# 06_Servo_Motor_ICs.net
KiCad netlist of a schematic drawn in Altium Designer
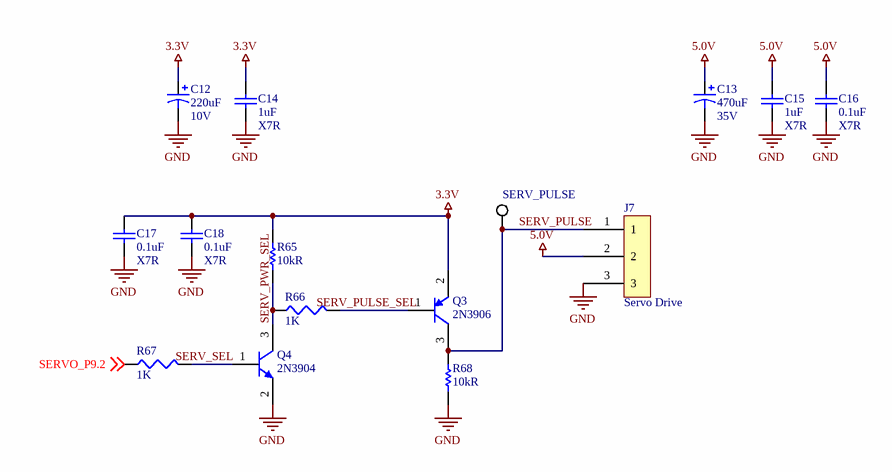
[diagram p0: 06_Servo_Motor_ICs.SchDoc]

(export (version "E")
  (design (tool "Eeschema 10.0.6"))
  (components
    (comp (ref "C12")
      (value "220uF")
      (footprint "CAPPR2-5x11")
      (description "Capacitor Al 105deg 220uF 10V 5X11")
      (fields
        (field (name "MANUFACTURER") "Rubycon")
        (field (name "MANUFACTURER PART NUMBER") "10YXJ220M5X11")
        (field (name "VOLTAGE") "10V")
      )
      (libsource (lib "ECE453") (part "Cap Pol1_1"))
    )
    (comp (ref "C13")
      (value "470uF")
      (footprint "CAPPR5-10x12.5")
      (description "CAP ALUM 470UF 20% 35V RADIAL")
      (fields
        (field (name "VOLTAGE") "35V")
        (field (name "MANUFACTURER") "Rubycon")
        (field (name "TOLERANCE") "20%")
      )
      (libsource (lib "ECE453") (part "Cap Pol3_1"))
    )
    (comp (ref "C14")
      (value "1uF")
      (footprint "CAP_0805")
      (description "CAP CER 1UF 50V X7R 0805")
      (fields
        (field (name "MANUFACTURER") "Samsung")
        (field (name "MANUFACTURER PART NUMBER") "CL21B105KBFNNNE")
        (field (name "DIELECTRIC") "X7R")
      )
      (libsource (lib "ECE453") (part "Cap_5"))
    )
    (comp (ref "C15")
      (value "1uF")
      (footprint "CAP_0805")
      (description "CAP CER 1UF 50V X7R 0805")
      (fields
        (field (name "MANUFACTURER") "Samsung")
        (field (name "MANUFACTURER PART NUMBER") "CL21B105KBFNNNE")
        (field (name "DIELECTRIC") "X7R")
      )
      (libsource (lib "ECE453") (part "Cap_5"))
    )
    (comp (ref "C16")
      (value "0.1uF")
      (footprint "CAP_0805")
      (description "Cap Ceramic 0.1uF 50V X7R 20% SMD 0805 125°C Plastic T/R")
      (fields
        (field (name "MANUFACTURER") "KEMET")
        (field (name "MANUFACTURER PART NUMBER") "C0805C104M5RAC7210")
        (field (name "DIELECTRIC") "X7R")
      )
      (libsource (lib "ECE453") (part "Cap_1"))
    )
    (comp (ref "C17")
      (value "0.1uF")
      (footprint "CAP_0805")
      (description "Cap Ceramic 0.1uF 50V X7R 20% SMD 0805 125°C Plastic T/R")
      (fields
        (field (name "MANUFACTURER") "KEMET")
        (field (name "MANUFACTURER PART NUMBER") "C0805C104M5RAC7210")
        (field (name "DIELECTRIC") "X7R")
      )
      (libsource (lib "ECE453") (part "Cap_1"))
    )
    (comp (ref "C18")
      (value "0.1uF")
      (footprint "CAP_0805")
      (description "Cap Ceramic 0.1uF 50V X7R 20% SMD 0805 125°C Plastic T/R")
      (fields
        (field (name "MANUFACTURER") "KEMET")
        (field (name "MANUFACTURER PART NUMBER") "C0805C104M5RAC7210")
        (field (name "DIELECTRIC") "X7R")
      )
      (libsource (lib "ECE453") (part "Cap_1"))
    )
    (comp (ref "J7")
      (value "Servo Drive")
      (footprint "3X1HDR")
      (description "Switch Slide N.O./N.C. SPDT Top Slide 0.2A 30VDC PC Pins Thru-Hole")
      (fields (field (name "MANUFACTURER") "E-Switch") (field (name "MANUFACTURER PART NUMBER") "EG1218"))
      (libsource (lib "ECE453") (part "3-Pin_1"))
    )
    (comp (ref "Q3")
      (value "2N3906")
      (footprint "SOT23-3M")
      (description "TRANS PNP 40V 0.2A SOT23")
      (fields
        (field (name "MANUFACTURER PART NUMBER") "MMBT3906LT1G")
        (field (name "MANUFACTURER") "ON Semiconductor")
      )
      (libsource (lib "ECE453") (part "2N3906"))
    )
    (comp (ref "Q4")
      (value "2N3904")
      (footprint "SOT23-3M")
      (description "NPN General Purpose Amplifier")
      (fields
        (field (name "MANUFACTURER PART NUMBER") "MMBT3904-7-F")
        (field (name "MANUFACTURER") "Diodes Incorporated")
      )
      (libsource (lib "ECE453") (part "2N3904"))
    )
    (comp (ref "R65")
      (value "RC0805FR-0710KL")
      (footprint "RESC2013X60X35NL10T20")
      (description "Chip Resistor, 10 KOhm, +/- 1%, 0.125 W, -55 to 155 degC, 0805 (2012 Metric), RoHS, Tape and Reel")
      (fields
        (field (name "MANUFACTURER") "Yageo")
        (field (name "TOLERANCE") "1%")
        (field (name "RESISTANCE") "10kR")
      )
      (libsource (lib "ECE453") (part "CMP-1659-00013-4"))
    )
    (comp (ref "R66")
      (value "1K")
      (footprint "ECE453:RES_0805")
      (description "Res Thick Film 0805 1K Ohm 1% 0.125W(1/8W) ±100ppm/C Pad SMD Automotive T/R")
      (fields
        (field (name "MANUFACTURER") "Stackpole Electronics")
        (field (name "MANUFACTURER PART NUMBER") "RMCF0805FT1K00")
      )
      (libsource (lib "ECE453") (part "Res3_1"))
    )
    (comp (ref "R67")
      (value "1K")
      (footprint "ECE453:RES_0805")
      (description "Res Thick Film 0805 1K Ohm 1% 0.125W(1/8W) ±100ppm/C Pad SMD Automotive T/R")
      (fields
        (field (name "MANUFACTURER") "Stackpole Electronics")
        (field (name "MANUFACTURER PART NUMBER") "RMCF0805FT1K00")
      )
      (libsource (lib "ECE453") (part "Res3_1"))
    )
    (comp (ref "R68")
      (value "RC0805FR-0710KL")
      (footprint "RESC2013X60X35NL10T20")
      (description "Chip Resistor, 10 KOhm, +/- 1%, 0.125 W, -55 to 155 degC, 0805 (2012 Metric), RoHS, Tape and Reel")
      (fields
        (field (name "MANUFACTURER") "Yageo")
        (field (name "TOLERANCE") "1%")
        (field (name "RESISTANCE") "10kR")
      )
      (libsource (lib "ECE453") (part "CMP-1659-00013-4"))
    )
    (comp (ref "SERV_PULSE")
      (value "~")
      (footprint "KSTN-5019_V")
      (description "Test Point, 1 Position SMD, RoHS, Tape and Reel")
      (fields
        (field (name "MANUFACTURER") "Keystone Electronics")
        (field (name "MANUFACTURER PART NUMBER") "5019")
      )
      (libsource (lib "ECE453") (part "CMP-1672-00008-1"))
    )
  )
  (nets
    (net (code "1") (name "/SERV_PULSE") (class "Default")
      (node (ref "J7") (pin "1") (pinfunction "1_1") (pintype "passive"))
      (node (ref "Q3") (pin "3") (pinfunction "C_3") (pintype "passive"))
      (node (ref "R68") (pin "2") (pinfunction "2_2") (pintype "passive"))
      (node (ref "SERV_PULSE") (pin "1") (pinfunction "1_1") (pintype "passive"))
    )
    (net (code "2") (name "/SERV_PULSE_SEL") (class "Default")
      (node (ref "Q3") (pin "1") (pinfunction "B_1") (pintype "passive"))
      (node (ref "R66") (pin "2") (pinfunction "2_2") (pintype "passive"))
    )
    (net (code "3") (name "/SERV_PWR_SEL") (class "Default")
      (node (ref "Q4") (pin "3") (pinfunction "C_3") (pintype "passive"))
      (node (ref "R65") (pin "1") (pinfunction "1_1") (pintype "passive"))
      (node (ref "R66") (pin "1") (pinfunction "1_1") (pintype "passive"))
    )
    (net (code "4") (name "/SERV_SEL") (class "Default")
      (node (ref "Q4") (pin "1") (pinfunction "B_1") (pintype "passive"))
      (node (ref "R67") (pin "2") (pinfunction "2_2") (pintype "passive"))
    )
    (net (code "5") (name "3.3V") (class "Default")
      (node (ref "C12") (pin "1") (pinfunction "1_1") (pintype "passive"))
      (node (ref "C14") (pin "2") (pinfunction "2_2") (pintype "passive"))
      (node (ref "C17") (pin "1") (pinfunction "1_1") (pintype "passive"))
      (node (ref "C18") (pin "2") (pinfunction "2_2") (pintype "passive"))
      (node (ref "Q3") (pin "2") (pinfunction "E_2") (pintype "passive"))
      (node (ref "R65") (pin "2") (pinfunction "2_2") (pintype "passive"))
    )
    (net (code "6") (name "5.0V") (class "Default")
      (node (ref "C13") (pin "1") (pinfunction "1_1") (pintype "passive"))
      (node (ref "C15") (pin "2") (pinfunction "2_2") (pintype "passive"))
      (node (ref "C16") (pin "2") (pinfunction "2_2") (pintype "passive"))
      (node (ref "J7") (pin "2") (pinfunction "2_2") (pintype "passive"))
    )
    (net (code "7") (name "GND") (class "Default")
      (node (ref "C12") (pin "2") (pinfunction "2_2") (pintype "passive"))
      (node (ref "C13") (pin "2") (pinfunction "2_2") (pintype "passive"))
      (node (ref "C14") (pin "1") (pinfunction "1_1") (pintype "passive"))
      (node (ref "C15") (pin "1") (pinfunction "1_1") (pintype "passive"))
      (node (ref "C16") (pin "1") (pinfunction "1_1") (pintype "passive"))
      (node (ref "C17") (pin "2") (pinfunction "2_2") (pintype "passive"))
      (node (ref "C18") (pin "1") (pinfunction "1_1") (pintype "passive"))
      (node (ref "J7") (pin "3") (pinfunction "3_3") (pintype "passive"))
      (node (ref "Q4") (pin "2") (pinfunction "E_2") (pintype "passive"))
      (node (ref "R68") (pin "1") (pinfunction "1_1") (pintype "passive"))
    )
    (net (code "8") (name "SERVO_P9.2") (class "Default")
      (node (ref "R67") (pin "1") (pinfunction "1_1") (pintype "passive"))
    )
  )
)
